# SCH_ECE198-12.net
KiCad netlist of a schematic drawn in EasyEDA
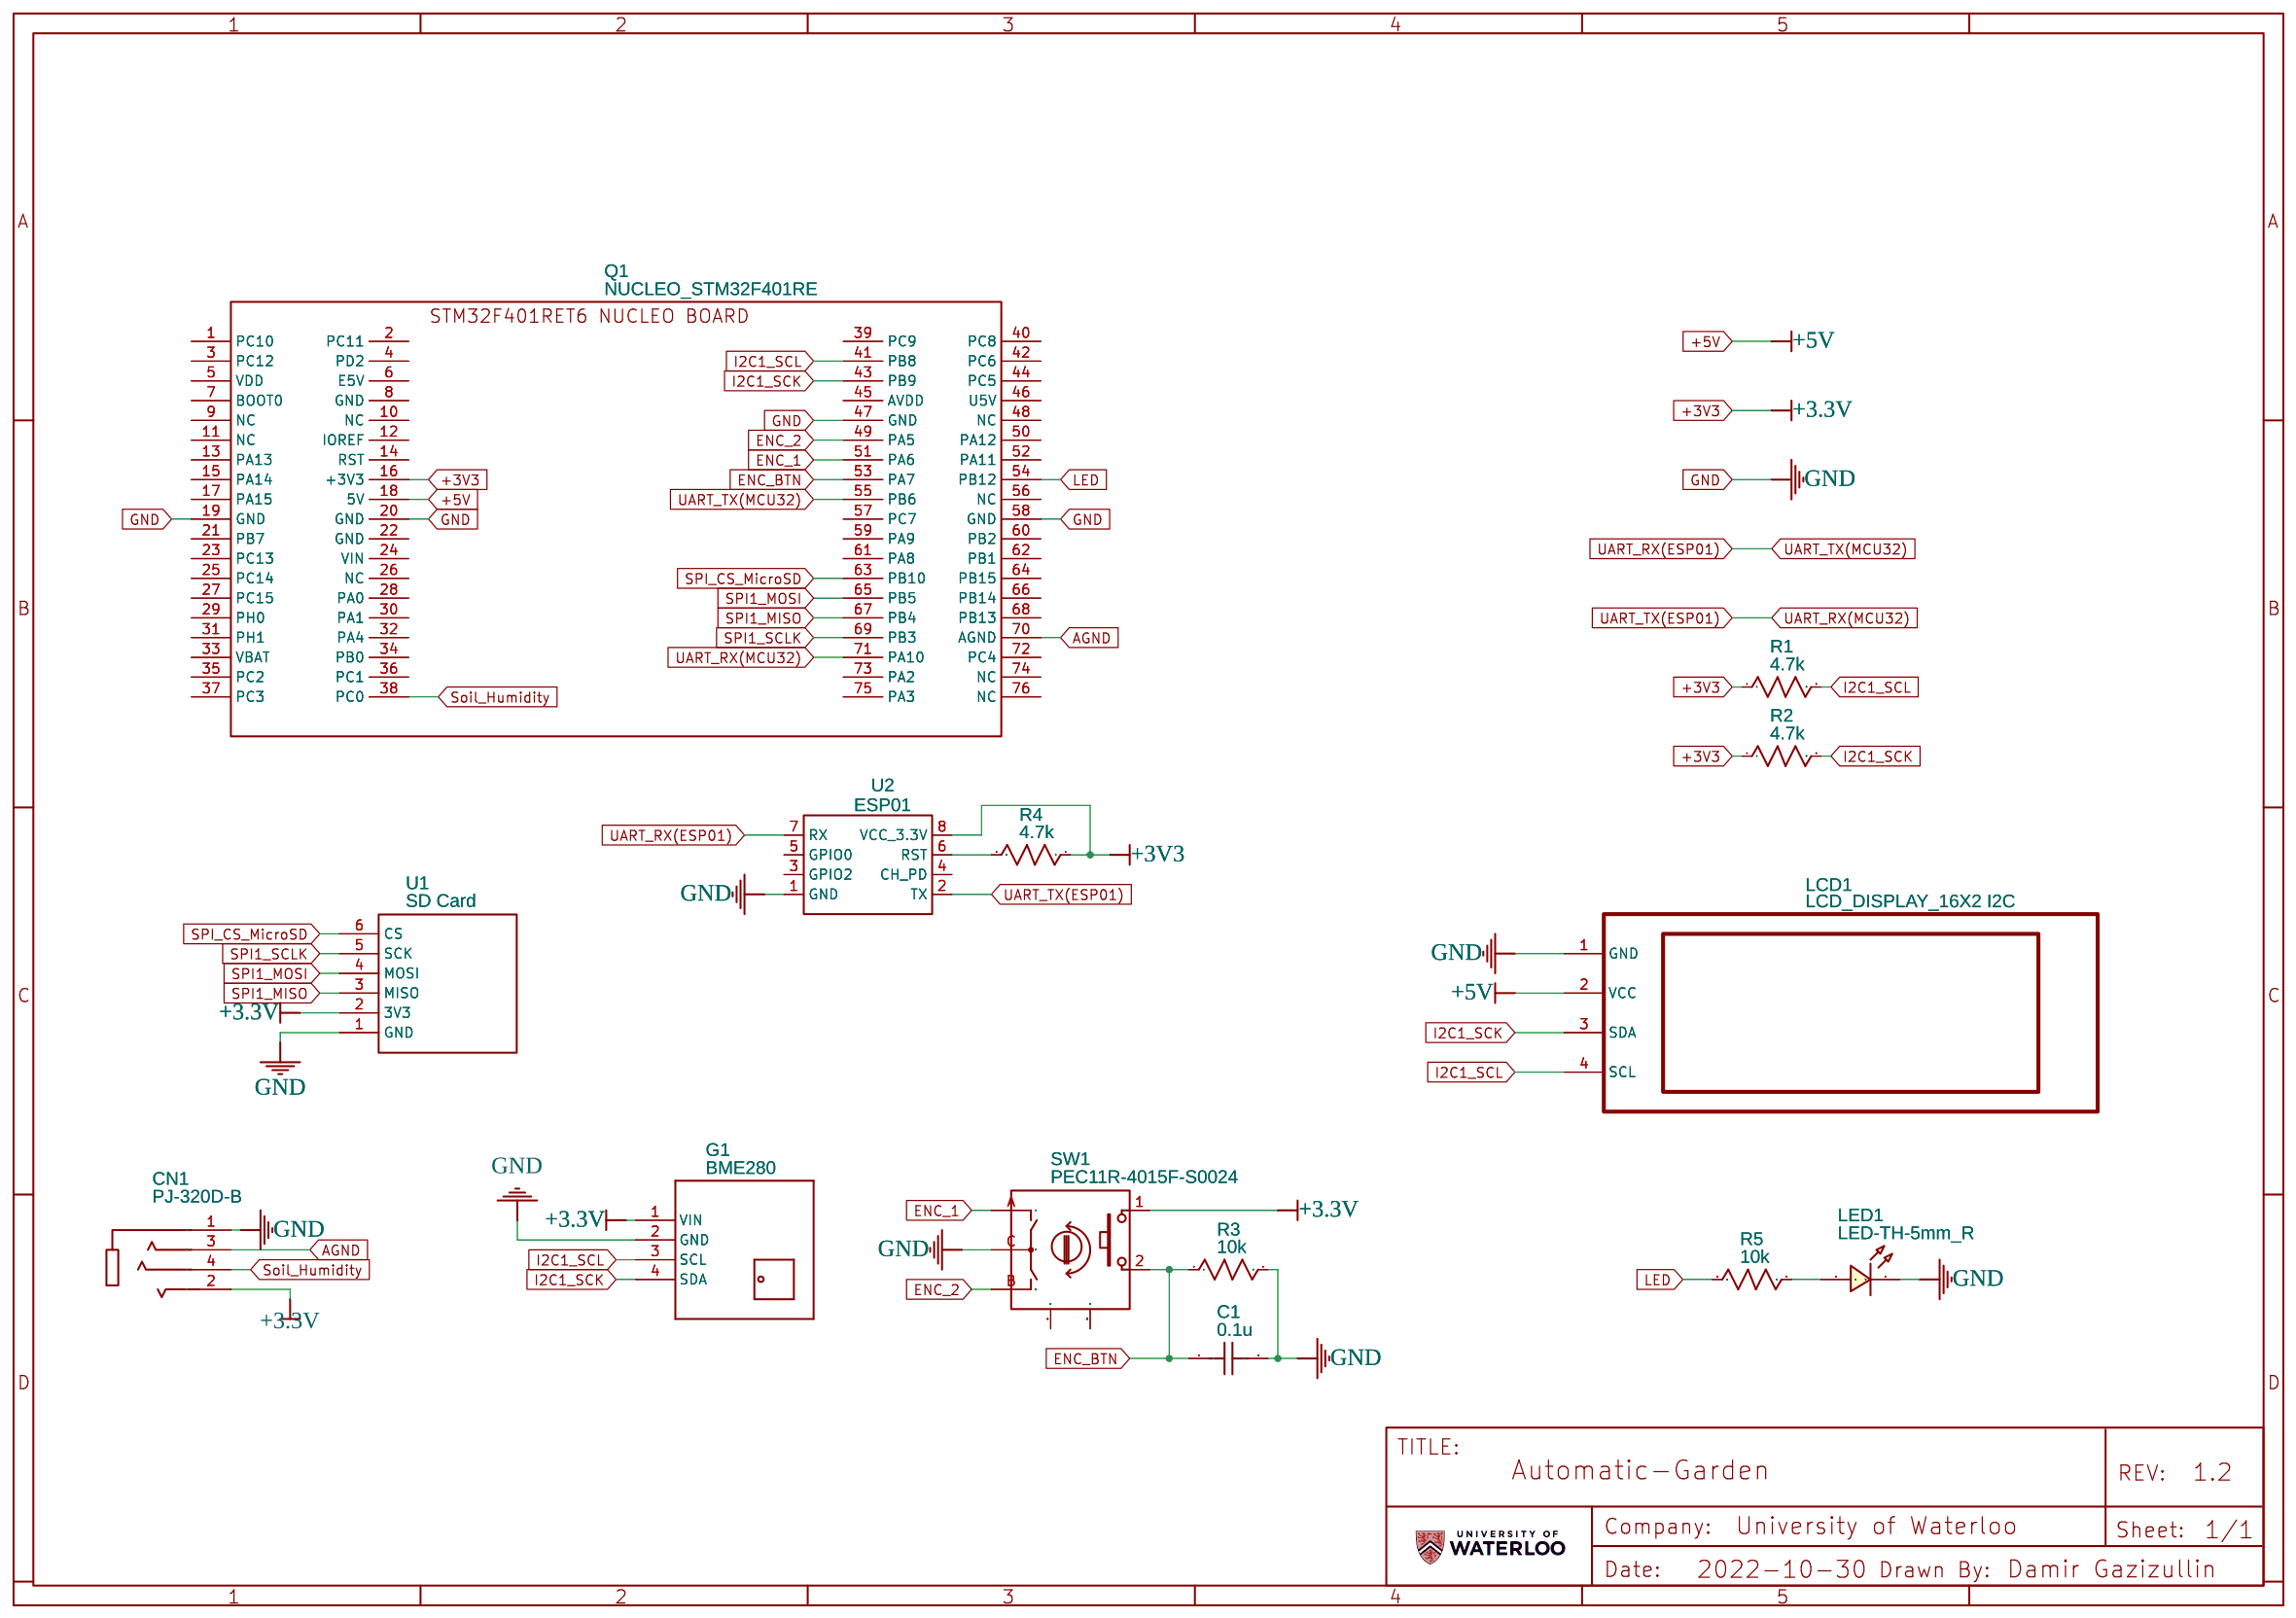
[diagram p0: schematic sheet]

(export (version "E")
  (design (tool "Eeschema 10.0.6"))
  (components
    (comp (ref "C1") (value "0.1u") (libsource (lib "") (part "C_0603_US")))
    (comp (ref "CN1")
      (value "PJ-320D-B")
      (fields (field (name "BOM_Supplier Part") "C2884940"))
      (libsource (lib "") (part "PJ-320D-B"))
    )
    (comp (ref "G1") (value "BME280") (libsource (lib "") (part "TEMP-HUM-PRES-BME280")))
    (comp (ref "LCD1") (value "LCD_DISPLAY_16X2 I2C") (libsource (lib "") (part "LCD_DISPLAY_16X2 I2C")))
    (comp (ref "LED1")
      (value "LED-TH-5mm_R")
      (fields
        (field (name "BOM_Manufacturer Part") "333-2SURD/S530-A3")
        (field (name "BOM_Supplier Part") "C87271")
      )
      (libsource (lib "") (part "LED-TH-5mm_R"))
    )
    (comp (ref "Q1") (value "NUCLEO_STM32F401RE") (libsource (lib "") (part "NUCLEO_STM32F401RE")))
    (comp (ref "R1") (value "4.7k") (libsource (lib "") (part "R_0603_US")))
    (comp (ref "R2") (value "4.7k") (libsource (lib "") (part "R_0603_US")))
    (comp (ref "R3") (value "10k") (libsource (lib "") (part "R_AXIAL-0.5_US")))
    (comp (ref "R4") (value "4.7k") (libsource (lib "") (part "R_AXIAL-0.5_US_1")))
    (comp (ref "R5") (value "10k") (libsource (lib "") (part "R_AXIAL-0.5_US_1")))
    (comp (ref "SW1")
      (value "PEC11R-4015F-S0024")
      (fields (field (name "BOM_Supplier Part") "C143789"))
      (libsource (lib "") (part "PEC11R-4015F-S0024"))
    )
    (comp (ref "U1") (value "SD Card") (libsource (lib "") (part "SD Card")))
    (comp (ref "U2")
      (value "ESP01")
      (fields
        (field (name "BOM_Manufacturer Part") "Header-Male-2.54_2x3")
        (field (name "BOM_Supplier Part") "C65114")
      )
      (libsource (lib "") (part "MODUL_ESP01"))
    )
  )
  (nets
    (net (code "1") (name "+3V3") (class "Default")
      (node (ref "CN1") (pin "2") (pinfunction "2_2") (pintype "unspecified"))
      (node (ref "G1") (pin "1") (pinfunction "VIN_1") (pintype "bidirectional"))
      (node (ref "Q1") (pin "16") (pinfunction "+3V3_16") (pintype "unspecified"))
      (node (ref "R1") (pin "1") (pinfunction "1_1") (pintype "unspecified"))
      (node (ref "R2") (pin "1") (pinfunction "1_1") (pintype "unspecified"))
      (node (ref "R4") (pin "1") (pinfunction "1_1") (pintype "unspecified"))
      (node (ref "SW1") (pin "1") (pinfunction "1_1") (pintype "unspecified"))
      (node (ref "U1") (pin "2") (pinfunction "3V3_2") (pintype "unspecified"))
      (node (ref "U2") (pin "8") (pinfunction "VCC_3.3V_8") (pintype "input"))
    )
    (net (code "2") (name "+5V") (class "Default")
      (node (ref "LCD1") (pin "2") (pinfunction "VCC_2") (pintype "passive"))
      (node (ref "Q1") (pin "18") (pinfunction "5V_18") (pintype "unspecified"))
    )
    (net (code "3") (name "AGND") (class "Default")
      (node (ref "CN1") (pin "3") (pinfunction "3_3") (pintype "unspecified"))
      (node (ref "Q1") (pin "70") (pinfunction "AGND_70") (pintype "unspecified"))
    )
    (net (code "4") (name "ENC_1") (class "Default")
      (node (ref "Q1") (pin "51") (pinfunction "PA6_51") (pintype "unspecified"))
      (node (ref "SW1") (pin "A") (pinfunction "A_A") (pintype "unspecified"))
    )
    (net (code "5") (name "ENC_2") (class "Default")
      (node (ref "Q1") (pin "49") (pinfunction "PA5_49") (pintype "unspecified"))
      (node (ref "SW1") (pin "B") (pinfunction "B_B") (pintype "unspecified"))
    )
    (net (code "6") (name "ENC_BTN") (class "Default")
      (node (ref "C1") (pin "1") (pinfunction "1_1") (pintype "unspecified"))
      (node (ref "Q1") (pin "53") (pinfunction "PA7_53") (pintype "unspecified"))
      (node (ref "R3") (pin "1") (pinfunction "1_1") (pintype "unspecified"))
      (node (ref "SW1") (pin "2") (pinfunction "2_2") (pintype "unspecified"))
    )
    (net (code "7") (name "GND") (class "Default")
      (node (ref "C1") (pin "2") (pinfunction "2_2") (pintype "unspecified"))
      (node (ref "CN1") (pin "1") (pinfunction "1_1") (pintype "unspecified"))
      (node (ref "G1") (pin "2") (pinfunction "GND_2") (pintype "bidirectional"))
      (node (ref "LCD1") (pin "1") (pinfunction "GND_1") (pintype "passive"))
      (node (ref "LED1") (pin "2") (pinfunction "2_2") (pintype "unspecified"))
      (node (ref "Q1") (pin "19") (pinfunction "GND_19") (pintype "unspecified"))
      (node (ref "Q1") (pin "20") (pinfunction "GND_20") (pintype "unspecified"))
      (node (ref "Q1") (pin "47") (pinfunction "GND_47") (pintype "unspecified"))
      (node (ref "Q1") (pin "58") (pinfunction "GND_58") (pintype "unspecified"))
      (node (ref "R3") (pin "2") (pinfunction "2_2") (pintype "unspecified"))
      (node (ref "SW1") (pin "C") (pinfunction "C_C") (pintype "unspecified"))
      (node (ref "U1") (pin "1") (pinfunction "GND_1") (pintype "unspecified"))
      (node (ref "U2") (pin "1") (pinfunction "GND_1") (pintype "input"))
    )
    (net (code "8") (name "I2C1_SCK") (class "Default")
      (node (ref "G1") (pin "4") (pinfunction "SDA_4") (pintype "bidirectional"))
      (node (ref "LCD1") (pin "3") (pinfunction "SDA_3") (pintype "passive"))
      (node (ref "Q1") (pin "43") (pinfunction "PB9_43") (pintype "unspecified"))
      (node (ref "R2") (pin "2") (pinfunction "2_2") (pintype "unspecified"))
    )
    (net (code "9") (name "I2C1_SCL") (class "Default")
      (node (ref "G1") (pin "3") (pinfunction "SCL_3") (pintype "bidirectional"))
      (node (ref "LCD1") (pin "4") (pinfunction "SCL_4") (pintype "passive"))
      (node (ref "Q1") (pin "41") (pinfunction "PB8_41") (pintype "unspecified"))
      (node (ref "R1") (pin "2") (pinfunction "2_2") (pintype "unspecified"))
    )
    (net (code "10") (name "LED") (class "Default")
      (node (ref "Q1") (pin "54") (pinfunction "PB12_54") (pintype "unspecified"))
      (node (ref "R5") (pin "2") (pinfunction "2_2") (pintype "unspecified"))
    )
    (net (code "11") (name "Net-(LED1-Pad1)") (class "Default")
      (node (ref "LED1") (pin "1") (pinfunction "1_1") (pintype "unspecified"))
      (node (ref "R5") (pin "1") (pinfunction "1_1") (pintype "unspecified"))
    )
    (net (code "12") (name "Net-(U2-RST)") (class "Default")
      (node (ref "R4") (pin "2") (pinfunction "2_2") (pintype "unspecified"))
      (node (ref "U2") (pin "6") (pinfunction "RST_6") (pintype "input"))
    )
    (net (code "13") (name "SPI1_MISO") (class "Default")
      (node (ref "Q1") (pin "67") (pinfunction "PB4_67") (pintype "unspecified"))
      (node (ref "U1") (pin "3") (pinfunction "MISO_3") (pintype "unspecified"))
    )
    (net (code "14") (name "SPI1_MOSI") (class "Default")
      (node (ref "Q1") (pin "65") (pinfunction "PB5_65") (pintype "unspecified"))
      (node (ref "U1") (pin "4") (pinfunction "MOSI_4") (pintype "unspecified"))
    )
    (net (code "15") (name "SPI1_SCLK") (class "Default")
      (node (ref "Q1") (pin "69") (pinfunction "PB3_69") (pintype "unspecified"))
      (node (ref "U1") (pin "5") (pinfunction "SCK_5") (pintype "unspecified"))
    )
    (net (code "16") (name "SPI_CS_MicroSD") (class "Default")
      (node (ref "Q1") (pin "63") (pinfunction "PB10_63") (pintype "unspecified"))
      (node (ref "U1") (pin "6") (pinfunction "CS_6") (pintype "unspecified"))
    )
    (net (code "17") (name "Soil_Humidity") (class "Default")
      (node (ref "CN1") (pin "4") (pinfunction "4_4") (pintype "unspecified"))
      (node (ref "Q1") (pin "38") (pinfunction "PC0_38") (pintype "unspecified"))
    )
    (net (code "18") (name "UART_RX(ESP01)") (class "Default")
      (node (ref "Q1") (pin "55") (pinfunction "PB6_55") (pintype "unspecified"))
      (node (ref "U2") (pin "7") (pinfunction "RX_7") (pintype "input"))
    )
    (net (code "19") (name "UART_RX(MCU32)") (class "Default")
      (node (ref "Q1") (pin "71") (pinfunction "PA10_71") (pintype "unspecified"))
      (node (ref "U2") (pin "2") (pinfunction "TX_2") (pintype "input"))
    )
    (net (code "20") (name "unconnected-(Q1-AVDD-Pad45)") (class "Default")
      (node (ref "Q1") (pin "45") (pinfunction "AVDD_45") (pintype "unspecified"))
    )
    (net (code "21") (name "unconnected-(Q1-BOOT0-Pad7)") (class "Default")
      (node (ref "Q1") (pin "7") (pinfunction "BOOT0_7") (pintype "unspecified"))
    )
    (net (code "22") (name "unconnected-(Q1-E5V-Pad6)") (class "Default")
      (node (ref "Q1") (pin "6") (pinfunction "E5V_6") (pintype "unspecified"))
    )
    (net (code "23") (name "unconnected-(Q1-GND-Pad8)") (class "Default")
      (node (ref "Q1") (pin "8") (pinfunction "GND_8") (pintype "unspecified"))
    )
    (net (code "24") (name "unconnected-(Q1-GND-Pad22)") (class "Default")
      (node (ref "Q1") (pin "22") (pinfunction "GND_22") (pintype "unspecified"))
    )
    (net (code "25") (name "unconnected-(Q1-IOREF-Pad12)") (class "Default")
      (node (ref "Q1") (pin "12") (pinfunction "IOREF_12") (pintype "unspecified"))
    )
    (net (code "26") (name "unconnected-(Q1-NC-Pad9)") (class "Default")
      (node (ref "Q1") (pin "9") (pinfunction "NC_9") (pintype "unspecified"))
    )
    (net (code "27") (name "unconnected-(Q1-NC-Pad10)") (class "Default")
      (node (ref "Q1") (pin "10") (pinfunction "NC_10") (pintype "unspecified"))
    )
    (net (code "28") (name "unconnected-(Q1-NC-Pad11)") (class "Default")
      (node (ref "Q1") (pin "11") (pinfunction "NC_11") (pintype "unspecified"))
    )
    (net (code "29") (name "unconnected-(Q1-NC-Pad26)") (class "Default")
      (node (ref "Q1") (pin "26") (pinfunction "NC_26") (pintype "unspecified"))
    )
    (net (code "30") (name "unconnected-(Q1-NC-Pad48)") (class "Default")
      (node (ref "Q1") (pin "48") (pinfunction "NC_48") (pintype "unspecified"))
    )
    (net (code "31") (name "unconnected-(Q1-NC-Pad56)") (class "Default")
      (node (ref "Q1") (pin "56") (pinfunction "NC_56") (pintype "unspecified"))
    )
    (net (code "32") (name "unconnected-(Q1-NC-Pad74)") (class "Default")
      (node (ref "Q1") (pin "74") (pinfunction "NC_74") (pintype "unspecified"))
    )
    (net (code "33") (name "unconnected-(Q1-NC-Pad76)") (class "Default")
      (node (ref "Q1") (pin "76") (pinfunction "NC_76") (pintype "unspecified"))
    )
    (net (code "34") (name "unconnected-(Q1-PA0-Pad28)") (class "Default")
      (node (ref "Q1") (pin "28") (pinfunction "PA0_28") (pintype "unspecified"))
    )
    (net (code "35") (name "unconnected-(Q1-PA1-Pad30)") (class "Default")
      (node (ref "Q1") (pin "30") (pinfunction "PA1_30") (pintype "unspecified"))
    )
    (net (code "36") (name "unconnected-(Q1-PA2-Pad73)") (class "Default")
      (node (ref "Q1") (pin "73") (pinfunction "PA2_73") (pintype "unspecified"))
    )
    (net (code "37") (name "unconnected-(Q1-PA3-Pad75)") (class "Default")
      (node (ref "Q1") (pin "75") (pinfunction "PA3_75") (pintype "unspecified"))
    )
    (net (code "38") (name "unconnected-(Q1-PA4-Pad32)") (class "Default")
      (node (ref "Q1") (pin "32") (pinfunction "PA4_32") (pintype "unspecified"))
    )
    (net (code "39") (name "unconnected-(Q1-PA8-Pad61)") (class "Default")
      (node (ref "Q1") (pin "61") (pinfunction "PA8_61") (pintype "unspecified"))
    )
    (net (code "40") (name "unconnected-(Q1-PA9-Pad59)") (class "Default")
      (node (ref "Q1") (pin "59") (pinfunction "PA9_59") (pintype "unspecified"))
    )
    (net (code "41") (name "unconnected-(Q1-PA11-Pad52)") (class "Default")
      (node (ref "Q1") (pin "52") (pinfunction "PA11_52") (pintype "unspecified"))
    )
    (net (code "42") (name "unconnected-(Q1-PA12-Pad50)") (class "Default")
      (node (ref "Q1") (pin "50") (pinfunction "PA12_50") (pintype "unspecified"))
    )
    (net (code "43") (name "unconnected-(Q1-PA13-Pad13)") (class "Default")
      (node (ref "Q1") (pin "13") (pinfunction "PA13_13") (pintype "unspecified"))
    )
    (net (code "44") (name "unconnected-(Q1-PA14-Pad15)") (class "Default")
      (node (ref "Q1") (pin "15") (pinfunction "PA14_15") (pintype "unspecified"))
    )
    (net (code "45") (name "unconnected-(Q1-PA15-Pad17)") (class "Default")
      (node (ref "Q1") (pin "17") (pinfunction "PA15_17") (pintype "unspecified"))
    )
    (net (code "46") (name "unconnected-(Q1-PB0-Pad34)") (class "Default")
      (node (ref "Q1") (pin "34") (pinfunction "PB0_34") (pintype "unspecified"))
    )
    (net (code "47") (name "unconnected-(Q1-PB1-Pad62)") (class "Default")
      (node (ref "Q1") (pin "62") (pinfunction "PB1_62") (pintype "unspecified"))
    )
    (net (code "48") (name "unconnected-(Q1-PB2-Pad60)") (class "Default")
      (node (ref "Q1") (pin "60") (pinfunction "PB2_60") (pintype "unspecified"))
    )
    (net (code "49") (name "unconnected-(Q1-PB7-Pad21)") (class "Default")
      (node (ref "Q1") (pin "21") (pinfunction "PB7_21") (pintype "unspecified"))
    )
    (net (code "50") (name "unconnected-(Q1-PB13-Pad68)") (class "Default")
      (node (ref "Q1") (pin "68") (pinfunction "PB13_68") (pintype "unspecified"))
    )
    (net (code "51") (name "unconnected-(Q1-PB14-Pad66)") (class "Default")
      (node (ref "Q1") (pin "66") (pinfunction "PB14_66") (pintype "unspecified"))
    )
    (net (code "52") (name "unconnected-(Q1-PB15-Pad64)") (class "Default")
      (node (ref "Q1") (pin "64") (pinfunction "PB15_64") (pintype "unspecified"))
    )
    (net (code "53") (name "unconnected-(Q1-PC1-Pad36)") (class "Default")
      (node (ref "Q1") (pin "36") (pinfunction "PC1_36") (pintype "unspecified"))
    )
    (net (code "54") (name "unconnected-(Q1-PC2-Pad35)") (class "Default")
      (node (ref "Q1") (pin "35") (pinfunction "PC2_35") (pintype "unspecified"))
    )
    (net (code "55") (name "unconnected-(Q1-PC3-Pad37)") (class "Default")
      (node (ref "Q1") (pin "37") (pinfunction "PC3_37") (pintype "unspecified"))
    )
    (net (code "56") (name "unconnected-(Q1-PC4-Pad72)") (class "Default")
      (node (ref "Q1") (pin "72") (pinfunction "PC4_72") (pintype "unspecified"))
    )
    (net (code "57") (name "unconnected-(Q1-PC5-Pad44)") (class "Default")
      (node (ref "Q1") (pin "44") (pinfunction "PC5_44") (pintype "unspecified"))
    )
    (net (code "58") (name "unconnected-(Q1-PC6-Pad42)") (class "Default")
      (node (ref "Q1") (pin "42") (pinfunction "PC6_42") (pintype "unspecified"))
    )
    (net (code "59") (name "unconnected-(Q1-PC7-Pad57)") (class "Default")
      (node (ref "Q1") (pin "57") (pinfunction "PC7_57") (pintype "unspecified"))
    )
    (net (code "60") (name "unconnected-(Q1-PC8-Pad40)") (class "Default")
      (node (ref "Q1") (pin "40") (pinfunction "PC8_40") (pintype "unspecified"))
    )
    (net (code "61") (name "unconnected-(Q1-PC9-Pad39)") (class "Default")
      (node (ref "Q1") (pin "39") (pinfunction "PC9_39") (pintype "unspecified"))
    )
    (net (code "62") (name "unconnected-(Q1-PC10-Pad1)") (class "Default")
      (node (ref "Q1") (pin "1") (pinfunction "PC10_1") (pintype "unspecified"))
    )
    (net (code "63") (name "unconnected-(Q1-PC11-Pad2)") (class "Default")
      (node (ref "Q1") (pin "2") (pinfunction "PC11_2") (pintype "unspecified"))
    )
    (net (code "64") (name "unconnected-(Q1-PC12-Pad3)") (class "Default")
      (node (ref "Q1") (pin "3") (pinfunction "PC12_3") (pintype "unspecified"))
    )
    (net (code "65") (name "unconnected-(Q1-PC13-Pad23)") (class "Default")
      (node (ref "Q1") (pin "23") (pinfunction "PC13_23") (pintype "unspecified"))
    )
    (net (code "66") (name "unconnected-(Q1-PC14-Pad25)") (class "Default")
      (node (ref "Q1") (pin "25") (pinfunction "PC14_25") (pintype "unspecified"))
    )
    (net (code "67") (name "unconnected-(Q1-PC15-Pad27)") (class "Default")
      (node (ref "Q1") (pin "27") (pinfunction "PC15_27") (pintype "unspecified"))
    )
    (net (code "68") (name "unconnected-(Q1-PD2-Pad4)") (class "Default")
      (node (ref "Q1") (pin "4") (pinfunction "PD2_4") (pintype "unspecified"))
    )
    (net (code "69") (name "unconnected-(Q1-PH0-Pad29)") (class "Default")
      (node (ref "Q1") (pin "29") (pinfunction "PH0_29") (pintype "unspecified"))
    )
    (net (code "70") (name "unconnected-(Q1-PH1-Pad31)") (class "Default")
      (node (ref "Q1") (pin "31") (pinfunction "PH1_31") (pintype "unspecified"))
    )
    (net (code "71") (name "unconnected-(Q1-RST-Pad14)") (class "Default")
      (node (ref "Q1") (pin "14") (pinfunction "RST_14") (pintype "unspecified"))
    )
    (net (code "72") (name "unconnected-(Q1-U5V-Pad46)") (class "Default")
      (node (ref "Q1") (pin "46") (pinfunction "U5V_46") (pintype "unspecified"))
    )
    (net (code "73") (name "unconnected-(Q1-VBAT-Pad33)") (class "Default")
      (node (ref "Q1") (pin "33") (pinfunction "VBAT_33") (pintype "unspecified"))
    )
    (net (code "74") (name "unconnected-(Q1-VDD-Pad5)") (class "Default")
      (node (ref "Q1") (pin "5") (pinfunction "VDD_5") (pintype "unspecified"))
    )
    (net (code "75") (name "unconnected-(Q1-VIN-Pad24)") (class "Default")
      (node (ref "Q1") (pin "24") (pinfunction "VIN_24") (pintype "unspecified"))
    )
    (net (code "76") (name "unconnected-(SW1-PadMT1)") (class "Default")
      (node (ref "SW1") (pin "MT1") (pinfunction "MT1_MT1") (pintype "unspecified"))
    )
    (net (code "77") (name "unconnected-(SW1-PadMT2)") (class "Default")
      (node (ref "SW1") (pin "MT2") (pinfunction "MT2_MT2") (pintype "unspecified"))
    )
    (net (code "78") (name "unconnected-(U2-CH_PD-Pad4)") (class "Default")
      (node (ref "U2") (pin "4") (pinfunction "CH_PD_4") (pintype "input"))
    )
    (net (code "79") (name "unconnected-(U2-GPIO0-Pad5)") (class "Default")
      (node (ref "U2") (pin "5") (pinfunction "GPIO0_5") (pintype "input"))
    )
    (net (code "80") (name "unconnected-(U2-GPIO2-Pad3)") (class "Default")
      (node (ref "U2") (pin "3") (pinfunction "GPIO2_3") (pintype "input"))
    )
  )
)
